# BeagleBone_Blue.net
KiCad netlist of a schematic drawn in EAGLE
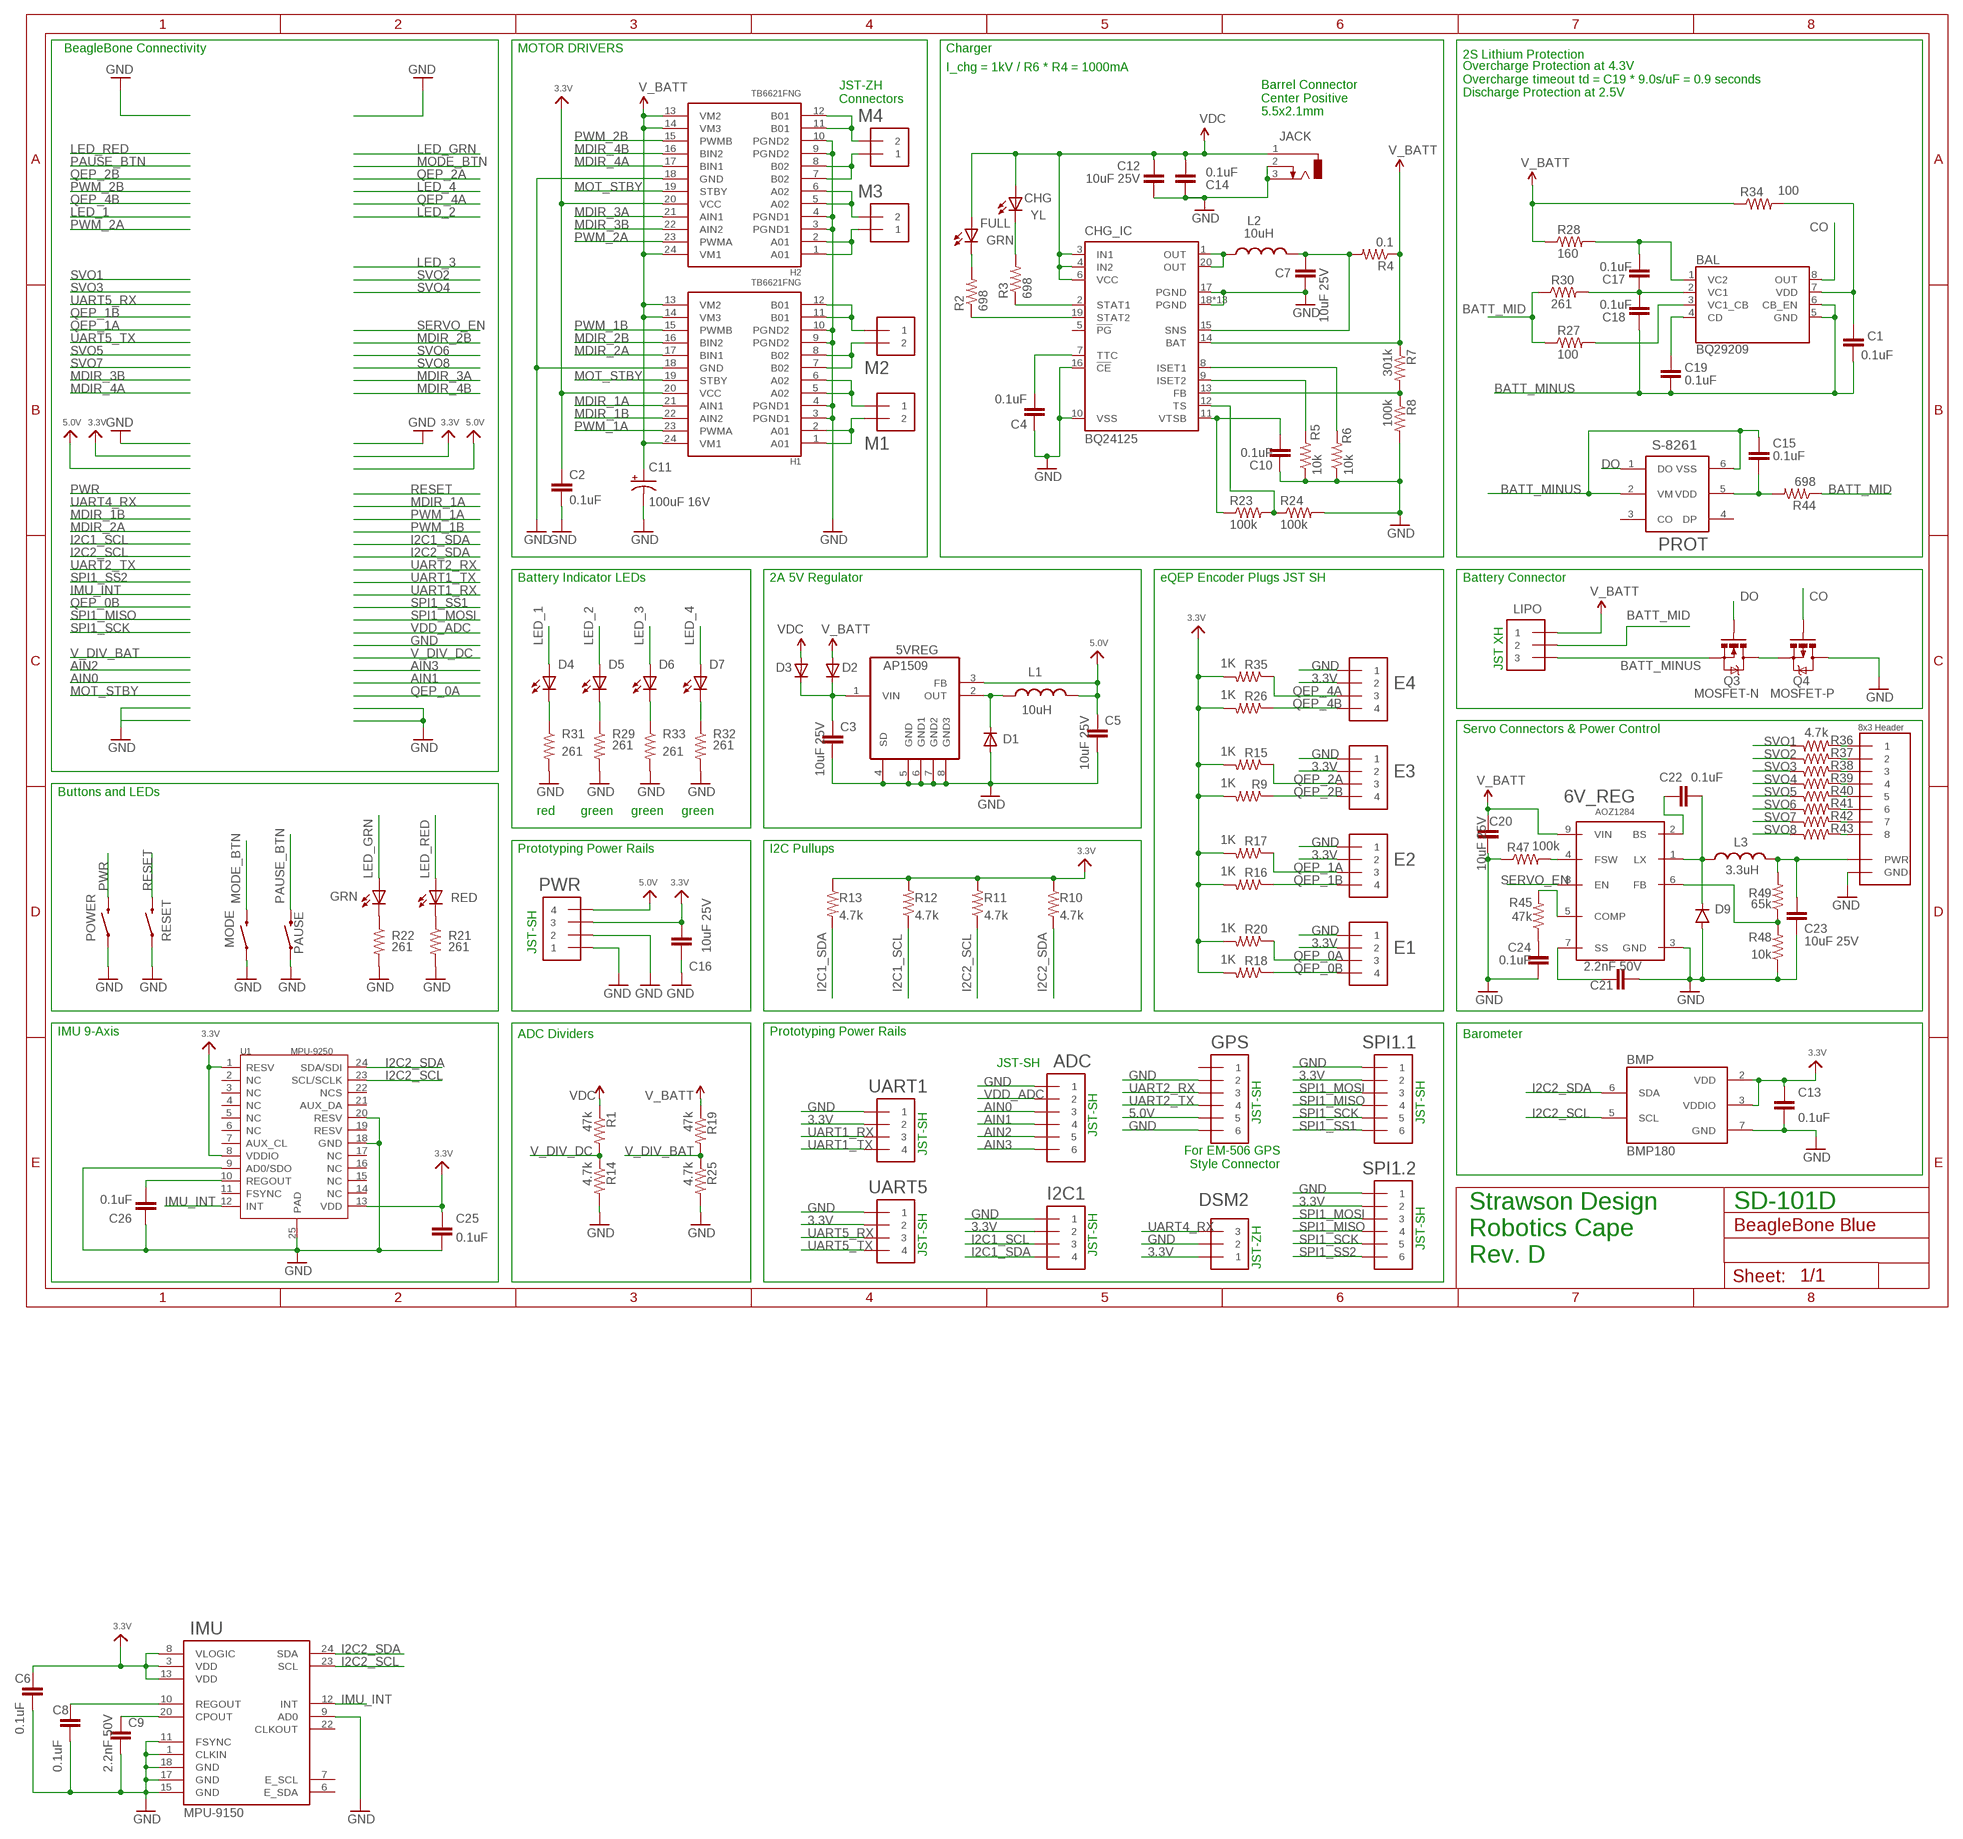
[diagram p0: schematic, sheet 1]

(export (version "E")
  (design (tool "Eeschema 10.0.6"))
  (components
    (comp (ref "5VREG")
      (value "AP1509SOIC-8-TIGHT")
      (footprint "eagle-import:SO08-TIGHT")
      (libsource (lib "eagle-import") (part "AP1509SOIC-8-TIGHT"))
    )
    (comp (ref "6V_REG")
      (value "AOZ1284")
      (footprint "eagle-import:SO08-EXPOSED")
      (libsource (lib "eagle-import") (part "AOZ1284"))
    )
    (comp (ref "ADC")
      (value "JST_SH_6")
      (footprint "eagle-import:JST_SH_6")
      (libsource (lib "eagle-import") (part "JST_SH_6"))
    )
    (comp (ref "BAL")
      (value "BQ29209")
      (footprint "eagle-import:8-SON_3X3MM")
      (libsource (lib "eagle-import") (part "BQ29209"))
    )
    (comp (ref "BMP")
      (value "BMP180")
      (footprint "eagle-import:BMP180")
      (libsource (lib "eagle-import") (part "BMP180"))
    )
    (comp (ref "C1")
      (value "0.1uF")
      (footprint "eagle-import:0402-CAP")
      (libsource (lib "eagle-import") (part "Strawson_Eagle_Lib_CAP0402-CAP"))
    )
    (comp (ref "C2")
      (value "0.1uF")
      (footprint "eagle-import:0402-CAP")
      (libsource (lib "eagle-import") (part "Strawson_Eagle_Lib_CAP0402-CAP"))
    )
    (comp (ref "C3")
      (value "10uF 25V")
      (footprint "eagle-import:0805")
      (libsource (lib "eagle-import") (part "CAP0805"))
    )
    (comp (ref "C4")
      (value "0.1uF")
      (footprint "eagle-import:0402-CAP")
      (libsource (lib "eagle-import") (part "Strawson_Eagle_Lib_CAP0402-CAP"))
    )
    (comp (ref "C5")
      (value "10uF 25V")
      (footprint "eagle-import:0805")
      (libsource (lib "eagle-import") (part "CAP0805"))
    )
    (comp (ref "C6")
      (value "0.1uF")
      (footprint "eagle-import:0402-CAP")
      (libsource (lib "eagle-import") (part "Strawson_Eagle_Lib_CAP0402-CAP"))
    )
    (comp (ref "C7")
      (value "10uF 25V")
      (footprint "eagle-import:0805")
      (libsource (lib "eagle-import") (part "CAP0805"))
    )
    (comp (ref "C8")
      (value "0.1uF")
      (footprint "eagle-import:0402-CAP")
      (libsource (lib "eagle-import") (part "Strawson_Eagle_Lib_CAP0402-CAP"))
    )
    (comp (ref "C9")
      (value "2.2nF 50V")
      (footprint "eagle-import:0402-CAP")
      (libsource (lib "eagle-import") (part "Strawson_Eagle_Lib_CAP0402-CAP"))
    )
    (comp (ref "C10")
      (value "0.1uF")
      (footprint "eagle-import:0402-CAP")
      (libsource (lib "eagle-import") (part "Strawson_Eagle_Lib_CAP0402-CAP"))
    )
    (comp (ref "C11")
      (value "100uF 16V")
      (footprint "eagle-import:PANASONIC_D")
      (libsource (lib "eagle-import") (part "CPOL-USD"))
    )
    (comp (ref "C12")
      (value "10uF 25V")
      (footprint "eagle-import:0805")
      (libsource (lib "eagle-import") (part "CAP0805"))
    )
    (comp (ref "C13")
      (value "0.1uF")
      (footprint "eagle-import:0402-CAP")
      (libsource (lib "eagle-import") (part "Strawson_Eagle_Lib_CAP0402-CAP"))
    )
    (comp (ref "C14")
      (value "0.1uF")
      (footprint "eagle-import:0402-CAP")
      (libsource (lib "eagle-import") (part "Strawson_Eagle_Lib_CAP0402-CAP"))
    )
    (comp (ref "C15")
      (value "0.1uF")
      (footprint "eagle-import:0402-CAP")
      (libsource (lib "eagle-import") (part "Strawson_Eagle_Lib_CAP0402-CAP"))
    )
    (comp (ref "C16")
      (value "10uF 25V")
      (footprint "eagle-import:0805")
      (libsource (lib "eagle-import") (part "CAP0805"))
    )
    (comp (ref "C17")
      (value "0.1uF")
      (footprint "eagle-import:0402-CAP")
      (libsource (lib "eagle-import") (part "Strawson_Eagle_Lib_CAP0402-CAP"))
    )
    (comp (ref "C18")
      (value "0.1uF")
      (footprint "eagle-import:0402-CAP")
      (libsource (lib "eagle-import") (part "Strawson_Eagle_Lib_CAP0402-CAP"))
    )
    (comp (ref "C19")
      (value "0.1uF")
      (footprint "eagle-import:0402-CAP")
      (libsource (lib "eagle-import") (part "Strawson_Eagle_Lib_CAP0402-CAP"))
    )
    (comp (ref "C20")
      (value "10uF 25V")
      (footprint "eagle-import:0805")
      (libsource (lib "eagle-import") (part "CAP0805"))
    )
    (comp (ref "C21")
      (value "2.2nF 50V")
      (footprint "eagle-import:0402-CAP")
      (libsource (lib "eagle-import") (part "Strawson_Eagle_Lib_CAP0402-CAP"))
    )
    (comp (ref "C22")
      (value "0.1uF")
      (footprint "eagle-import:0402-CAP")
      (libsource (lib "eagle-import") (part "Strawson_Eagle_Lib_CAP0402-CAP"))
    )
    (comp (ref "C23")
      (value "10uF 25V")
      (footprint "eagle-import:0805")
      (libsource (lib "eagle-import") (part "CAP0805"))
    )
    (comp (ref "C24")
      (value "0.1uF")
      (footprint "eagle-import:0402-CAP")
      (libsource (lib "eagle-import") (part "Strawson_Eagle_Lib_CAP0402-CAP"))
    )
    (comp (ref "C25")
      (value "0.1uF")
      (footprint "eagle-import:0402-CAP")
      (libsource (lib "eagle-import") (part "Strawson_Eagle_Lib_CAP0402-CAP"))
    )
    (comp (ref "C26")
      (value "0.1uF")
      (footprint "eagle-import:0402-CAP")
      (libsource (lib "eagle-import") (part "Strawson_Eagle_Lib_CAP0402-CAP"))
    )
    (comp (ref "CHG")
      (value "YL")
      (footprint "eagle-import:LED-0603")
      (libsource (lib "eagle-import") (part "LED0603"))
    )
    (comp (ref "CHG_IC")
      (value "BQ24125")
      (footprint "eagle-import:QFN20_3,5X4,5")
      (fields (field (name "MPN") "BQ24125RHLR"))
      (libsource (lib "eagle-import") (part "BQ24125"))
    )
    (comp (ref "D1")
      (value "DIODESOD-123")
      (footprint "eagle-import:SOD-123")
      (libsource (lib "eagle-import") (part "DIODESOD-123"))
    )
    (comp (ref "D2")
      (value "DIODESOD-123")
      (footprint "eagle-import:SOD-123")
      (libsource (lib "eagle-import") (part "DIODESOD-123"))
    )
    (comp (ref "D3")
      (value "DIODESOD-123")
      (footprint "eagle-import:SOD-123")
      (libsource (lib "eagle-import") (part "DIODESOD-123"))
    )
    (comp (ref "D4")
      (value "RED")
      (footprint "eagle-import:LED-0603")
      (libsource (lib "eagle-import") (part "LED0603"))
    )
    (comp (ref "D5")
      (value "GREEN")
      (footprint "eagle-import:LED-0603")
      (libsource (lib "eagle-import") (part "LED0603"))
    )
    (comp (ref "D6")
      (value "GREEN")
      (footprint "eagle-import:LED-0603")
      (libsource (lib "eagle-import") (part "LED0603"))
    )
    (comp (ref "D7")
      (value "GREEN")
      (footprint "eagle-import:LED-0603")
      (libsource (lib "eagle-import") (part "LED0603"))
    )
    (comp (ref "D9")
      (value "DIODEDO214AA")
      (footprint "eagle-import:DO-214AA")
      (libsource (lib "eagle-import") (part "DIODEDO214AA"))
    )
    (comp (ref "DSM2")
      (value "JST_ZH_3")
      (footprint "eagle-import:JST_ZH_3")
      (libsource (lib "eagle-import") (part "JST_ZH_3"))
    )
    (comp (ref "E1")
      (value "JST_SH_4")
      (footprint "eagle-import:JST_SH_4_SMD")
      (libsource (lib "eagle-import") (part "JST_SH_4"))
    )
    (comp (ref "E2")
      (value "JST_SH_4")
      (footprint "eagle-import:JST_SH_4_SMD")
      (libsource (lib "eagle-import") (part "JST_SH_4"))
    )
    (comp (ref "E3")
      (value "JST_SH_4")
      (footprint "eagle-import:JST_SH_4_SMD")
      (libsource (lib "eagle-import") (part "JST_SH_4"))
    )
    (comp (ref "E4")
      (value "JST_SH_4")
      (footprint "eagle-import:JST_SH_4_SMD")
      (libsource (lib "eagle-import") (part "JST_SH_4"))
    )
    (comp (ref "FULL")
      (value "GRN")
      (footprint "eagle-import:LED-0603")
      (libsource (lib "eagle-import") (part "LED0603"))
    )
    (comp (ref "GPS")
      (value "JST_SH_6")
      (footprint "eagle-import:JST_SH_6")
      (libsource (lib "eagle-import") (part "JST_SH_6"))
    )
    (comp (ref "GRN")
      (value "GRN")
      (footprint "eagle-import:LED-0603")
      (libsource (lib "eagle-import") (part "LED0603"))
    )
    (comp (ref "H1")
      (value "TB6621FNG")
      (footprint "eagle-import:SSOP24")
      (libsource (lib "eagle-import") (part "TB6621FNG"))
    )
    (comp (ref "H2")
      (value "TB6621FNG")
      (footprint "eagle-import:SSOP24")
      (libsource (lib "eagle-import") (part "TB6621FNG"))
    )
    (comp (ref "I2C1")
      (value "JST_SH_4")
      (footprint "eagle-import:JST_SH_4_SMD")
      (libsource (lib "eagle-import") (part "JST_SH_4"))
    )
    (comp (ref "IMU")
      (value "MPU-9150")
      (footprint "eagle-import:QFN-24-NP")
      (libsource (lib "eagle-import") (part "MPU-9150QFN-24-NP"))
    )
    (comp (ref "JACK")
      (value "5.5x2.1mm")
      (footprint "eagle-import:DCJ0303")
      (libsource (lib "eagle-import") (part "DCJ0303"))
    )
    (comp (ref "L1")
      (value "10uH")
      (footprint "eagle-import:SRN6045")
      (libsource (lib "eagle-import") (part "INDUCTORBOURNS_SRN6045"))
    )
    (comp (ref "L2")
      (value "10uH")
      (footprint "eagle-import:SRN6045")
      (libsource (lib "eagle-import") (part "INDUCTORBOURNS_SRN6045"))
    )
    (comp (ref "L3")
      (value "3.3uH")
      (footprint "eagle-import:8X8MM_INDUCTOR")
      (libsource (lib "eagle-import") (part "INDUCTOR"))
    )
    (comp (ref "LIPO")
      (value "JST_XH_3-PIN")
      (footprint "eagle-import:JST_XH_3-PIN")
      (libsource (lib "eagle-import") (part "JST_XH_3-PIN"))
    )
    (comp (ref "M1")
      (value "JST_ZH_2")
      (footprint "eagle-import:JST_ZH_2")
      (libsource (lib "eagle-import") (part "JST_ZH_2"))
    )
    (comp (ref "M2")
      (value "JST_ZH_2")
      (footprint "eagle-import:JST_ZH_2")
      (libsource (lib "eagle-import") (part "JST_ZH_2"))
    )
    (comp (ref "M3")
      (value "JST_ZH_2")
      (footprint "eagle-import:JST_ZH_2")
      (libsource (lib "eagle-import") (part "JST_ZH_2"))
    )
    (comp (ref "M4")
      (value "JST_ZH_2")
      (footprint "eagle-import:JST_ZH_2")
      (libsource (lib "eagle-import") (part "JST_ZH_2"))
    )
    (comp (ref "MODE")
      (value "SWITCH-MOMENTARY-2-SMD-1101NE")
      (footprint "eagle-import:TACTILE-SWITCH-1101NE")
      (libsource (lib "eagle-import") (part "SWITCH-MOMENTARY-2-SMD-1101NE"))
    )
    (comp (ref "PAUSE")
      (value "SWITCH-MOMENTARY-2-SMD-1101NE")
      (footprint "eagle-import:TACTILE-SWITCH-1101NE")
      (libsource (lib "eagle-import") (part "SWITCH-MOMENTARY-2-SMD-1101NE"))
    )
    (comp (ref "POWER")
      (value "SWITCH-MOMENTARY-2-SMD-1101NE")
      (footprint "eagle-import:TACTILE-SWITCH-1101NE")
      (libsource (lib "eagle-import") (part "SWITCH-MOMENTARY-2-SMD-1101NE"))
    )
    (comp (ref "PROT")
      (value "S-8261")
      (footprint "eagle-import:SOT-236")
      (libsource (lib "eagle-import") (part "S-8261"))
    )
    (comp (ref "PWR")
      (value "JST_SH_4")
      (footprint "eagle-import:JST_SH_4_SMD")
      (libsource (lib "eagle-import") (part "JST_SH_4"))
    )
    (comp (ref "Q3")
      (value "MOSFET-N")
      (footprint "eagle-import:SO08-TIGHT")
      (libsource (lib "eagle-import") (part "MOSFET-NCHANNEL"))
    )
    (comp (ref "Q4")
      (value "MOSFET-P")
      (footprint "eagle-import:SO08-TIGHT")
      (libsource (lib "eagle-import") (part "MOSFET-PCHANNEL"))
    )
    (comp (ref "R1")
      (value "47k")
      (footprint "eagle-import:0402-RES")
      (libsource (lib "eagle-import") (part "RESISTOR0402-RES"))
    )
    (comp (ref "R2")
      (value "698")
      (footprint "eagle-import:0402-RES")
      (libsource (lib "eagle-import") (part "RESISTOR0402-RES"))
    )
    (comp (ref "R3")
      (value "698")
      (footprint "eagle-import:0402-RES")
      (libsource (lib "eagle-import") (part "RESISTOR0402-RES"))
    )
    (comp (ref "R4")
      (value "0.1")
      (footprint "eagle-import:0603-RES")
      (libsource (lib "eagle-import") (part "RESISTOR0603"))
    )
    (comp (ref "R5")
      (value "10k")
      (footprint "eagle-import:0402-RES")
      (libsource (lib "eagle-import") (part "RESISTOR0402-RES"))
    )
    (comp (ref "R6")
      (value "10k")
      (footprint "eagle-import:0402-RES")
      (libsource (lib "eagle-import") (part "RESISTOR0402-RES"))
    )
    (comp (ref "R7")
      (value "301k")
      (footprint "eagle-import:0402-RES")
      (libsource (lib "eagle-import") (part "RESISTOR0402-RES"))
    )
    (comp (ref "R8")
      (value "100k")
      (footprint "eagle-import:0402-RES")
      (libsource (lib "eagle-import") (part "RESISTOR0402-RES"))
    )
    (comp (ref "R9")
      (value "1K")
      (footprint "eagle-import:0402-RES")
      (libsource (lib "eagle-import") (part "RESISTOR0402-RES"))
    )
    (comp (ref "R10")
      (value "4.7k")
      (footprint "eagle-import:0402-RES")
      (libsource (lib "eagle-import") (part "RESISTOR0402-RES"))
    )
    (comp (ref "R11")
      (value "4.7k")
      (footprint "eagle-import:0402-RES")
      (libsource (lib "eagle-import") (part "RESISTOR0402-RES"))
    )
    (comp (ref "R12")
      (value "4.7k")
      (footprint "eagle-import:0402-RES")
      (libsource (lib "eagle-import") (part "RESISTOR0402-RES"))
    )
    (comp (ref "R13")
      (value "4.7k")
      (footprint "eagle-import:0402-RES")
      (libsource (lib "eagle-import") (part "RESISTOR0402-RES"))
    )
    (comp (ref "R14")
      (value "4.7k")
      (footprint "eagle-import:0402-RES")
      (libsource (lib "eagle-import") (part "RESISTOR0402-RES"))
    )
    (comp (ref "R15")
      (value "1K")
      (footprint "eagle-import:0402-RES")
      (libsource (lib "eagle-import") (part "RESISTOR0402-RES"))
    )
    (comp (ref "R16")
      (value "1K")
      (footprint "eagle-import:0402-RES")
      (libsource (lib "eagle-import") (part "RESISTOR0402-RES"))
    )
    (comp (ref "R17")
      (value "1K")
      (footprint "eagle-import:0402-RES")
      (libsource (lib "eagle-import") (part "RESISTOR0402-RES"))
    )
    (comp (ref "R18")
      (value "1K")
      (footprint "eagle-import:0402-RES")
      (libsource (lib "eagle-import") (part "RESISTOR0402-RES"))
    )
    (comp (ref "R19")
      (value "47k")
      (footprint "eagle-import:0402-RES")
      (libsource (lib "eagle-import") (part "RESISTOR0402-RES"))
    )
    (comp (ref "R20")
      (value "1K")
      (footprint "eagle-import:0402-RES")
      (libsource (lib "eagle-import") (part "RESISTOR0402-RES"))
    )
    (comp (ref "R21")
      (value "261")
      (footprint "eagle-import:0402-RES")
      (libsource (lib "eagle-import") (part "RESISTOR0402-RES"))
    )
    (comp (ref "R22")
      (value "261")
      (footprint "eagle-import:0402-RES")
      (libsource (lib "eagle-import") (part "RESISTOR0402-RES"))
    )
    (comp (ref "R23")
      (value "100k")
      (footprint "eagle-import:0402-RES")
      (libsource (lib "eagle-import") (part "RESISTOR0402-RES"))
    )
    (comp (ref "R24")
      (value "100k")
      (footprint "eagle-import:0402-RES")
      (libsource (lib "eagle-import") (part "RESISTOR0402-RES"))
    )
    (comp (ref "R25")
      (value "4.7k")
      (footprint "eagle-import:0402-RES")
      (libsource (lib "eagle-import") (part "RESISTOR0402-RES"))
    )
    (comp (ref "R26")
      (value "1K")
      (footprint "eagle-import:0402-RES")
      (libsource (lib "eagle-import") (part "RESISTOR0402-RES"))
    )
    (comp (ref "R27")
      (value "100")
      (footprint "eagle-import:0402-RES")
      (libsource (lib "eagle-import") (part "RESISTOR0402-RES"))
    )
    (comp (ref "R28")
      (value "160")
      (footprint "eagle-import:0402-RES")
      (libsource (lib "eagle-import") (part "RESISTOR0402-RES"))
    )
    (comp (ref "R29")
      (value "261")
      (footprint "eagle-import:0402-RES")
      (libsource (lib "eagle-import") (part "RESISTOR0402-RES"))
    )
    (comp (ref "R30")
      (value "261")
      (footprint "eagle-import:0402-RES")
      (libsource (lib "eagle-import") (part "RESISTOR0402-RES"))
    )
    (comp (ref "R31")
      (value "261")
      (footprint "eagle-import:0402-RES")
      (libsource (lib "eagle-import") (part "RESISTOR0402-RES"))
    )
    (comp (ref "R32")
      (value "261")
      (footprint "eagle-import:0402-RES")
      (libsource (lib "eagle-import") (part "RESISTOR0402-RES"))
    )
    (comp (ref "R33")
      (value "261")
      (footprint "eagle-import:0402-RES")
      (libsource (lib "eagle-import") (part "RESISTOR0402-RES"))
    )
    (comp (ref "R34")
      (value "100")
      (footprint "eagle-import:0402-RES")
      (libsource (lib "eagle-import") (part "RESISTOR0402-RES"))
    )
    (comp (ref "R35")
      (value "1K")
      (footprint "eagle-import:0402-RES")
      (libsource (lib "eagle-import") (part "RESISTOR0402-RES"))
    )
    (comp (ref "R36")
      (value "4.7k")
      (footprint "eagle-import:0402-RES")
      (libsource (lib "eagle-import") (part "RESISTOR0402-RES"))
    )
    (comp (ref "R37")
      (value "4.7k")
      (footprint "eagle-import:0402-RES")
      (libsource (lib "eagle-import") (part "RESISTOR0402-RES"))
    )
    (comp (ref "R38")
      (value "4.7k")
      (footprint "eagle-import:0402-RES")
      (libsource (lib "eagle-import") (part "RESISTOR0402-RES"))
    )
    (comp (ref "R39")
      (value "4.7k")
      (footprint "eagle-import:0402-RES")
      (libsource (lib "eagle-import") (part "RESISTOR0402-RES"))
    )
    (comp (ref "R40")
      (value "4.7k")
      (footprint "eagle-import:0402-RES")
      (libsource (lib "eagle-import") (part "RESISTOR0402-RES"))
    )
    (comp (ref "R41")
      (value "4.7k")
      (footprint "eagle-import:0402-RES")
      (libsource (lib "eagle-import") (part "RESISTOR0402-RES"))
    )
    (comp (ref "R42")
      (value "4.7k")
      (footprint "eagle-import:0402-RES")
      (libsource (lib "eagle-import") (part "RESISTOR0402-RES"))
    )
    (comp (ref "R43")
      (value "4.7k")
      (footprint "eagle-import:0402-RES")
      (libsource (lib "eagle-import") (part "RESISTOR0402-RES"))
    )
    (comp (ref "R44")
      (value "698")
      (footprint "eagle-import:0402-RES")
      (libsource (lib "eagle-import") (part "RESISTOR0402-RES"))
    )
    (comp (ref "R45")
      (value "47k")
      (footprint "eagle-import:0402-RES")
      (libsource (lib "eagle-import") (part "RESISTOR0402-RES"))
    )
    (comp (ref "R47")
      (value "100k")
      (footprint "eagle-import:0402-RES")
      (libsource (lib "eagle-import") (part "RESISTOR0402-RES"))
    )
    (comp (ref "R48")
      (value "10k")
      (footprint "eagle-import:0402-RES")
      (libsource (lib "eagle-import") (part "RESISTOR0402-RES"))
    )
    (comp (ref "R49")
      (value "65k")
      (footprint "eagle-import:0402-RES")
      (libsource (lib "eagle-import") (part "RESISTOR0402-RES"))
    )
    (comp (ref "RED")
      (value "RED")
      (footprint "eagle-import:LED-0603")
      (libsource (lib "eagle-import") (part "LED0603"))
    )
    (comp (ref "RESET")
      (value "SWITCH-MOMENTARY-2-SMD-1101NE")
      (footprint "eagle-import:TACTILE-SWITCH-1101NE")
      (libsource (lib "eagle-import") (part "SWITCH-MOMENTARY-2-SMD-1101NE"))
    )
    (comp (ref "SPI1.1")
      (value "JST_SH_6")
      (footprint "eagle-import:JST_SH_6")
      (libsource (lib "eagle-import") (part "JST_SH_6"))
    )
    (comp (ref "SPI1.2")
      (value "JST_SH_6")
      (footprint "eagle-import:JST_SH_6")
      (libsource (lib "eagle-import") (part "JST_SH_6"))
    )
    (comp (ref "U$1")
      (value "SERVO_HEADERS_8X")
      (footprint "eagle-import:3X8_0.1__HEADER")
      (libsource (lib "eagle-import") (part "SERVO_HEADERS_8X"))
    )
    (comp (ref "U1")
      (value "MPU-9250")
      (footprint "eagle-import:QFN24G-0.4-3X3MM")
      (libsource (lib "eagle-import") (part "MPU-9250"))
    )
    (comp (ref "UART1")
      (value "JST_SH_4")
      (footprint "eagle-import:JST_SH_4_SMD")
      (libsource (lib "eagle-import") (part "JST_SH_4"))
    )
    (comp (ref "UART5")
      (value "JST_SH_4")
      (footprint "eagle-import:JST_SH_4_SMD")
      (libsource (lib "eagle-import") (part "JST_SH_4"))
    )
  )
  (nets
    (net (code "1") (name "/AIN0") (class "Default")
      (node (ref "ADC") (pin "3") (pinfunction "3_3") (pintype "bidirectional"))
    )
    (net (code "2") (name "/AIN1") (class "Default")
      (node (ref "ADC") (pin "4") (pinfunction "4_4") (pintype "bidirectional"))
    )
    (net (code "3") (name "/AIN2") (class "Default")
      (node (ref "ADC") (pin "5") (pinfunction "5_5") (pintype "bidirectional"))
    )
    (net (code "4") (name "/AIN3") (class "Default")
      (node (ref "ADC") (pin "6") (pinfunction "6_6") (pintype "bidirectional"))
    )
    (net (code "5") (name "/BATT_MID") (class "Default")
      (node (ref "LIPO") (pin "P$2") (pinfunction "2_P$2") (pintype "passive"))
      (node (ref "R27") (pin "1") (pinfunction "1_1") (pintype "passive"))
      (node (ref "R30") (pin "1") (pinfunction "1_1") (pintype "passive"))
      (node (ref "R44") (pin "1") (pinfunction "1_1") (pintype "passive"))
    )
    (net (code "6") (name "/BATT_MINUS") (class "Default")
      (node (ref "BAL") (pin "5") (pinfunction "GND_5") (pintype "bidirectional"))
      (node (ref "BAL") (pin "6") (pinfunction "CB_EN_6") (pintype "bidirectional"))
      (node (ref "C1") (pin "2") (pinfunction "2_2") (pintype "passive"))
      (node (ref "C15") (pin "1") (pinfunction "1_1") (pintype "passive"))
      (node (ref "C18") (pin "1") (pinfunction "1_1") (pintype "passive"))
      (node (ref "C19") (pin "2") (pinfunction "2_2") (pintype "passive"))
      (node (ref "LIPO") (pin "P$3") (pinfunction "3_P$3") (pintype "passive"))
      (node (ref "PROT") (pin "2") (pinfunction "VM_2") (pintype "bidirectional"))
      (node (ref "PROT") (pin "6") (pinfunction "VSS_6") (pintype "bidirectional"))
      (node (ref "Q3") (pin "1") (pinfunction "S_1") (pintype "passive"))
      (node (ref "Q3") (pin "2") (pinfunction "S_2") (pintype "passive"))
      (node (ref "Q3") (pin "3") (pinfunction "S_3") (pintype "passive"))
    )
    (net (code "7") (name "/CO") (class "Default")
      (node (ref "BAL") (pin "8") (pinfunction "OUT_8") (pintype "bidirectional"))
      (node (ref "Q4") (pin "4") (pinfunction "G_4") (pintype "passive"))
    )
    (net (code "8") (name "/DO") (class "Default")
      (node (ref "PROT") (pin "1") (pinfunction "DO_1") (pintype "bidirectional"))
      (node (ref "Q3") (pin "4") (pinfunction "G_4") (pintype "passive"))
    )
    (net (code "9") (name "/I2C1_SCL") (class "Default")
      (node (ref "I2C1") (pin "3") (pinfunction "3_3") (pintype "bidirectional"))
      (node (ref "R12") (pin "1") (pinfunction "1_1") (pintype "passive"))
    )
    (net (code "10") (name "/I2C1_SDA") (class "Default")
      (node (ref "I2C1") (pin "4") (pinfunction "4_4") (pintype "bidirectional"))
      (node (ref "R13") (pin "2") (pinfunction "2_2") (pintype "passive"))
    )
    (net (code "11") (name "/I2C2_SCL") (class "Default")
      (node (ref "BMP") (pin "5") (pinfunction "SCL_5") (pintype "input"))
      (node (ref "IMU") (pin "23") (pinfunction "SCL_23") (pintype "bidirectional"))
      (node (ref "R11") (pin "1") (pinfunction "1_1") (pintype "passive"))
      (node (ref "U1") (pin "23") (pinfunction "SCL/SCLK_23") (pintype "bidirectional"))
    )
    (net (code "12") (name "/I2C2_SDA") (class "Default")
      (node (ref "BMP") (pin "6") (pinfunction "SDA_6") (pintype "bidirectional"))
      (node (ref "IMU") (pin "24") (pinfunction "SDA_24") (pintype "bidirectional"))
      (node (ref "R10") (pin "2") (pinfunction "2_2") (pintype "passive"))
      (node (ref "U1") (pin "24") (pinfunction "SDA/SDI_24") (pintype "bidirectional"))
    )
    (net (code "13") (name "/IMU_INT") (class "Default")
      (node (ref "IMU") (pin "12") (pinfunction "INT_12") (pintype "bidirectional"))
      (node (ref "U1") (pin "12") (pinfunction "INT_12") (pintype "bidirectional"))
    )
    (net (code "14") (name "/LED_1") (class "Default")
      (node (ref "D4") (pin "A") (pinfunction "A_A") (pintype "passive"))
    )
    (net (code "15") (name "/LED_2") (class "Default")
      (node (ref "D5") (pin "A") (pinfunction "A_A") (pintype "passive"))
    )
    (net (code "16") (name "/LED_3") (class "Default")
      (node (ref "D6") (pin "A") (pinfunction "A_A") (pintype "passive"))
    )
    (net (code "17") (name "/LED_4") (class "Default")
      (node (ref "D7") (pin "A") (pinfunction "A_A") (pintype "passive"))
    )
    (net (code "18") (name "/LED_GRN") (class "Default")
      (node (ref "GRN") (pin "A") (pinfunction "A_A") (pintype "passive"))
    )
    (net (code "19") (name "/LED_RED") (class "Default")
      (node (ref "RED") (pin "A") (pinfunction "A_A") (pintype "passive"))
    )
    (net (code "20") (name "/MDIR_1A") (class "Default")
      (node (ref "H1") (pin "21") (pinfunction "AIN1_21") (pintype "bidirectional"))
    )
    (net (code "21") (name "/MDIR_1B") (class "Default")
      (node (ref "H1") (pin "22") (pinfunction "AIN2_22") (pintype "bidirectional"))
    )
    (net (code "22") (name "/MDIR_2A") (class "Default")
      (node (ref "H1") (pin "17") (pinfunction "BIN1_17") (pintype "bidirectional"))
    )
    (net (code "23") (name "/MDIR_2B") (class "Default")
      (node (ref "H1") (pin "16") (pinfunction "BIN2_16") (pintype "bidirectional"))
    )
    (net (code "24") (name "/MDIR_3A") (class "Default")
      (node (ref "H2") (pin "21") (pinfunction "AIN1_21") (pintype "bidirectional"))
    )
    (net (code "25") (name "/MDIR_3B") (class "Default")
      (node (ref "H2") (pin "22") (pinfunction "AIN2_22") (pintype "bidirectional"))
    )
    (net (code "26") (name "/MDIR_4A") (class "Default")
      (node (ref "H2") (pin "17") (pinfunction "BIN1_17") (pintype "bidirectional"))
    )
    (net (code "27") (name "/MDIR_4B") (class "Default")
      (node (ref "H2") (pin "16") (pinfunction "BIN2_16") (pintype "bidirectional"))
    )
    (net (code "28") (name "/MODE_BTN") (class "Default")
      (node (ref "MODE") (pin "P$2") (pinfunction "2_P$2") (pintype "passive"))
    )
    (net (code "29") (name "/MOT_STBY") (class "Default")
      (node (ref "H1") (pin "19") (pinfunction "STBY_19") (pintype "bidirectional"))
      (node (ref "H2") (pin "19") (pinfunction "STBY_19") (pintype "bidirectional"))
    )
    (net (code "30") (name "/PAUSE_BTN") (class "Default")
      (node (ref "PAUSE") (pin "P$2") (pinfunction "2_P$2") (pintype "passive"))
    )
    (net (code "31") (name "/PWM_1A") (class "Default")
      (node (ref "H1") (pin "23") (pinfunction "PWMA_23") (pintype "bidirectional"))
    )
    (net (code "32") (name "/PWM_1B") (class "Default")
      (node (ref "H1") (pin "15") (pinfunction "PWMB_15") (pintype "bidirectional"))
    )
    (net (code "33") (name "/PWM_2A") (class "Default")
      (node (ref "H2") (pin "23") (pinfunction "PWMA_23") (pintype "bidirectional"))
    )
    (net (code "34") (name "/PWM_2B") (class "Default")
      (node (ref "H2") (pin "15") (pinfunction "PWMB_15") (pintype "bidirectional"))
    )
    (net (code "35") (name "/PWR") (class "Default")
      (node (ref "POWER") (pin "P$2") (pinfunction "2_P$2") (pintype "passive"))
    )
    (net (code "36") (name "/QEP_0A") (class "Default")
      (node (ref "E1") (pin "3") (pinfunction "3_3") (pintype "bidirectional"))
      (node (ref "R20") (pin "1") (pinfunction "1_1") (pintype "passive"))
    )
    (net (code "37") (name "/QEP_0B") (class "Default")
      (node (ref "E1") (pin "4") (pinfunction "4_4") (pintype "bidirectional"))
      (node (ref "R18") (pin "1") (pinfunction "1_1") (pintype "passive"))
    )
    (net (code "38") (name "/QEP_1A") (class "Default")
      (node (ref "E2") (pin "3") (pinfunction "3_3") (pintype "bidirectional"))
      (node (ref "R17") (pin "1") (pinfunction "1_1") (pintype "passive"))
    )
    (net (code "39") (name "/QEP_1B") (class "Default")
      (node (ref "E2") (pin "4") (pinfunction "4_4") (pintype "bidirectional"))
      (node (ref "R16") (pin "1") (pinfunction "1_1") (pintype "passive"))
    )
    (net (code "40") (name "/QEP_2A") (class "Default")
      (node (ref "E3") (pin "3") (pinfunction "3_3") (pintype "bidirectional"))
      (node (ref "R15") (pin "1") (pinfunction "1_1") (pintype "passive"))
    )
    (net (code "41") (name "/QEP_2B") (class "Default")
      (node (ref "E3") (pin "4") (pinfunction "4_4") (pintype "bidirectional"))
      (node (ref "R9") (pin "1") (pinfunction "1_1") (pintype "passive"))
    )
    (net (code "42") (name "/QEP_4A") (class "Default")
      (node (ref "E4") (pin "3") (pinfunction "3_3") (pintype "bidirectional"))
      (node (ref "R35") (pin "1") (pinfunction "1_1") (pintype "passive"))
    )
    (net (code "43") (name "/QEP_4B") (class "Default")
      (node (ref "E4") (pin "4") (pinfunction "4_4") (pintype "bidirectional"))
      (node (ref "R26") (pin "1") (pinfunction "1_1") (pintype "passive"))
    )
    (net (code "44") (name "/RESET") (class "Default")
      (node (ref "RESET") (pin "P$2") (pinfunction "2_P$2") (pintype "passive"))
    )
    (net (code "45") (name "/SERVO_EN") (class "Default")
      (node (ref "6V_REG") (pin "8") (pinfunction "EN_8") (pintype "bidirectional"))
    )
    (net (code "46") (name "/SPI1_MISO") (class "Default")
      (node (ref "SPI1.1") (pin "4") (pinfunction "4_4") (pintype "bidirectional"))
      (node (ref "SPI1.2") (pin "4") (pinfunction "4_4") (pintype "bidirectional"))
    )
    (net (code "47") (name "/SPI1_MOSI") (class "Default")
      (node (ref "SPI1.1") (pin "3") (pinfunction "3_3") (pintype "bidirectional"))
      (node (ref "SPI1.2") (pin "3") (pinfunction "3_3") (pintype "bidirectional"))
    )
    (net (code "48") (name "/SPI1_SCK") (class "Default")
      (node (ref "SPI1.1") (pin "5") (pinfunction "5_5") (pintype "bidirectional"))
      (node (ref "SPI1.2") (pin "5") (pinfunction "5_5") (pintype "bidirectional"))
    )
    (net (code "49") (name "/SPI1_SS1") (class "Default")
      (node (ref "SPI1.1") (pin "6") (pinfunction "6_6") (pintype "bidirectional"))
    )
    (net (code "50") (name "/SPI1_SS2") (class "Default")
      (node (ref "SPI1.2") (pin "6") (pinfunction "6_6") (pintype "bidirectional"))
    )
    (net (code "51") (name "/SVO1") (class "Default")
      (node (ref "R36") (pin "1") (pinfunction "1_1") (pintype "passive"))
    )
    (net (code "52") (name "/SVO2") (class "Default")
      (node (ref "R37") (pin "1") (pinfunction "1_1") (pintype "passive"))
    )
    (net (code "53") (name "/SVO3") (class "Default")
      (node (ref "R38") (pin "1") (pinfunction "1_1") (pintype "passive"))
    )
    (net (code "54") (name "/SVO4") (class "Default")
      (node (ref "R39") (pin "1") (pinfunction "1_1") (pintype "passive"))
    )
    (net (code "55") (name "/SVO5") (class "Default")
      (node (ref "R40") (pin "1") (pinfunction "1_1") (pintype "passive"))
    )
    (net (code "56") (name "/SVO6") (class "Default")
      (node (ref "R41") (pin "1") (pinfunction "1_1") (pintype "passive"))
    )
    (net (code "57") (name "/SVO7") (class "Default")
      (node (ref "R42") (pin "1") (pinfunction "1_1") (pintype "passive"))
    )
    (net (code "58") (name "/SVO8") (class "Default")
      (node (ref "R43") (pin "1") (pinfunction "1_1") (pintype "passive"))
    )
    (net (code "59") (name "/UART1_RX") (class "Default")
      (node (ref "UART1") (pin "3") (pinfunction "3_3") (pintype "bidirectional"))
    )
    (net (code "60") (name "/UART1_TX") (class "Default")
      (node (ref "UART1") (pin "4") (pinfunction "4_4") (pintype "bidirectional"))
    )
    (net (code "61") (name "/UART2_RX") (class "Default")
      (node (ref "GPS") (pin "3") (pinfunction "3_3") (pintype "bidirectional"))
    )
    (net (code "62") (name "/UART2_TX") (class "Default")
      (node (ref "GPS") (pin "4") (pinfunction "4_4") (pintype "bidirectional"))
    )
    (net (code "63") (name "/UART4_RX") (class "Default")
      (node (ref "DSM2") (pin "P$3") (pinfunction "3_P$3") (pintype "bidirectional"))
    )
    (net (code "64") (name "/UART5_RX") (class "Default")
      (node (ref "UART5") (pin "3") (pinfunction "3_3") (pintype "bidirectional"))
    )
    (net (code "65") (name "/UART5_TX") (class "Default")
      (node (ref "UART5") (pin "4") (pinfunction "4_4") (pintype "bidirectional"))
    )
    (net (code "66") (name "/VDD_ADC") (class "Default")
      (node (ref "ADC") (pin "2") (pinfunction "2_2") (pintype "bidirectional"))
    )
    (net (code "67") (name "/V_DIV_BAT") (class "Default")
      (node (ref "R19") (pin "2") (pinfunction "2_2") (pintype "passive"))
      (node (ref "R25") (pin "1") (pinfunction "1_1") (pintype "passive"))
    )
    (net (code "68") (name "/V_DIV_DC") (class "Default")
      (node (ref "R1") (pin "2") (pinfunction "2_2") (pintype "passive"))
      (node (ref "R14") (pin "1") (pinfunction "1_1") (pintype "passive"))
    )
    (net (code "69") (name "3.3V") (class "Default")
      (node (ref "BMP") (pin "2") (pinfunction "VDD_2") (pintype "power_in"))
      (node (ref "BMP") (pin "3") (pinfunction "VDDIO_3") (pintype "power_in"))
      (node (ref "C13") (pin "1") (pinfunction "1_1") (pintype "passive"))
      (node (ref "C16") (pin "1") (pinfunction "1_1") (pintype "passive"))
      (node (ref "C2") (pin "2") (pinfunction "2_2") (pintype "passive"))
      (node (ref "C25") (pin "1") (pinfunction "1_1") (pintype "passive"))
      (node (ref "C6") (pin "1") (pinfunction "1_1") (pintype "passive"))
      (node (ref "DSM2") (pin "P$1") (pinfunction "1_P$1") (pintype "bidirectional"))
      (node (ref "E1") (pin "2") (pinfunction "2_2") (pintype "bidirectional"))
      (node (ref "E2") (pin "2") (pinfunction "2_2") (pintype "bidirectional"))
      (node (ref "E3") (pin "2") (pinfunction "2_2") (pintype "bidirectional"))
      (node (ref "E4") (pin "2") (pinfunction "2_2") (pintype "bidirectional"))
      (node (ref "H1") (pin "20") (pinfunction "VCC_20") (pintype "bidirectional"))
      (node (ref "H2") (pin "20") (pinfunction "VCC_20") (pintype "bidirectional"))
      (node (ref "I2C1") (pin "2") (pinfunction "2_2") (pintype "bidirectional"))
      (node (ref "IMU") (pin "13") (pinfunction "VDD_13") (pintype "bidirectional"))
      (node (ref "IMU") (pin "3") (pinfunction "VDD_3") (pintype "bidirectional"))
      (node (ref "IMU") (pin "8") (pinfunction "VLOGIC_8") (pintype "bidirectional"))
      (node (ref "PWR") (pin "3") (pinfunction "3_3") (pintype "bidirectional"))
      (node (ref "R10") (pin "1") (pinfunction "1_1") (pintype "passive"))
      (node (ref "R11") (pin "2") (pinfunction "2_2") (pintype "passive"))
      (node (ref "R12") (pin "2") (pinfunction "2_2") (pintype "passive"))
      (node (ref "R13") (pin "1") (pinfunction "1_1") (pintype "passive"))
      (node (ref "R15") (pin "2") (pinfunction "2_2") (pintype "passive"))
      (node (ref "R16") (pin "2") (pinfunction "2_2") (pintype "passive"))
      (node (ref "R17") (pin "2") (pinfunction "2_2") (pintype "passive"))
      (node (ref "R18") (pin "2") (pinfunction "2_2") (pintype "passive"))
      (node (ref "R20") (pin "2") (pinfunction "2_2") (pintype "passive"))
      (node (ref "R26") (pin "2") (pinfunction "2_2") (pintype "passive"))
      (node (ref "R35") (pin "2") (pinfunction "2_2") (pintype "passive"))
      (node (ref "R9") (pin "2") (pinfunction "2_2") (pintype "passive"))
      (node (ref "SPI1.1") (pin "2") (pinfunction "2_2") (pintype "bidirectional"))
      (node (ref "SPI1.2") (pin "2") (pinfunction "2_2") (pintype "bidirectional"))
      (node (ref "U1") (pin "1") (pinfunction "RESV_1") (pintype "bidirectional"))
      (node (ref "U1") (pin "13") (pinfunction "VDD_13") (pintype "bidirectional"))
      (node (ref "U1") (pin "8") (pinfunction "VDDIO_8") (pintype "bidirectional"))
      (node (ref "UART1") (pin "2") (pinfunction "2_2") (pintype "bidirectional"))
      (node (ref "UART5") (pin "2") (pinfunction "2_2") (pintype "bidirectional"))
    )
    (net (code "70") (name "5.0V") (class "Default")
      (node (ref "5VREG") (pin "3") (pinfunction "FB_3") (pintype "output"))
      (node (ref "C5") (pin "1") (pinfunction "1_1") (pintype "passive"))
      (node (ref "GPS") (pin "5") (pinfunction "5_5") (pintype "bidirectional"))
      (node (ref "L1") (pin "2") (pinfunction "2_2") (pintype "passive"))
      (node (ref "PWR") (pin "4") (pinfunction "4_4") (pintype "bidirectional"))
    )
    (net (code "71") (name "GND") (class "Default")
      (node (ref "5VREG") (pin "4") (pinfunction "SD_4") (pintype "input"))
      (node (ref "5VREG") (pin "5") (pinfunction "GND_5") (pintype "power_in"))
      (node (ref "5VREG") (pin "6") (pinfunction "GND1_6") (pintype "input"))
      (node (ref "5VREG") (pin "7") (pinfunction "GND2_7") (pintype "passive"))
      (node (ref "5VREG") (pin "8") (pinfunction "GND3_8") (pintype "power_in"))
      (node (ref "6V_REG") (pin "3") (pinfunction "GND_3") (pintype "bidirectional"))
      (node (ref "ADC") (pin "1") (pinfunction "1_1") (pintype "bidirectional"))
      (node (ref "BMP") (pin "7") (pinfunction "GND_7") (pintype "power_in"))
      (node (ref "C10") (pin "1") (pinfunction "1_1") (pintype "passive"))
      (node (ref "C11") (pin "-") (pinfunction "-_-") (pintype "passive"))
      (node (ref "C12") (pin "2") (pinfunction "2_2") (pintype "passive"))
      (node (ref "C13") (pin "2") (pinfunction "2_2") (pintype "passive"))
      (node (ref "C14") (pin "1") (pinfunction "1_1") (pintype "passive"))
      (node (ref "C16") (pin "2") (pinfunction "2_2") (pintype "passive"))
      (node (ref "C2") (pin "1") (pinfunction "1_1") (pintype "passive"))
      (node (ref "C20") (pin "1") (pinfunction "1_1") (pintype "passive"))
      (node (ref "C21") (pin "1") (pinfunction "1_1") (pintype "passive"))
      (node (ref "C23") (pin "1") (pinfunction "1_1") (pintype "passive"))
      (node (ref "C24") (pin "1") (pinfunction "1_1") (pintype "passive"))
      (node (ref "C25") (pin "2") (pinfunction "2_2") (pintype "passive"))
      (node (ref "C26") (pin "1") (pinfunction "1_1") (pintype "passive"))
      (node (ref "C3") (pin "2") (pinfunction "2_2") (pintype "passive"))
      (node (ref "C4") (pin "1") (pinfunction "1_1") (pintype "passive"))
      (node (ref "C5") (pin "2") (pinfunction "2_2") (pintype "passive"))
      (node (ref "C6") (pin "2") (pinfunction "2_2") (pintype "passive"))
      (node (ref "C7") (pin "2") (pinfunction "2_2") (pintype "passive"))
      (node (ref "C8") (pin "2") (pinfunction "2_2") (pintype "passive"))
      (node (ref "C9") (pin "2") (pinfunction "2_2") (pintype "passive"))
      (node (ref "CHG_IC") (pin "10") (pinfunction "VSS_10") (pintype "power_in"))
      (node (ref "CHG_IC") (pin "16") (pinfunction "~{CE}_16") (pintype "input"))
      (node (ref "CHG_IC") (pin "17") (pinfunction "PGND_17") (pintype "input"))
      (node (ref "CHG_IC") (pin "18") (pinfunction "PGND_18") (pintype "input"))
      (node (ref "CHG_IC") (pin "EXP") (pinfunction "PGND_EXP") (pintype "input"))
      (node (ref "CHG_IC") (pin "EXP@10") (pinfunction "PGND_EXP@10") (pintype "input"))
      (node (ref "CHG_IC") (pin "EXP@11") (pinfunction "PGND_EXP@11") (pintype "input"))
      (node (ref "CHG_IC") (pin "EXP@12") (pinfunction "PGND_EXP@12") (pintype "input"))
      (node (ref "CHG_IC") (pin "EXP@7") (pinfunction "PGND_EXP@7") (pintype "input"))
      (node (ref "CHG_IC") (pin "EXP@8") (pinfunction "PGND_EXP@8") (pintype "input"))
      (node (ref "CHG_IC") (pin "EXP@9") (pinfunction "PGND_EXP@9") (pintype "input"))
      (node (ref "CHG_IC") (pin "GND@1") (pinfunction "PGND_GND@1") (pintype "input"))
      (node (ref "CHG_IC") (pin "GND@2") (pinfunction "PGND_GND@2") (pintype "input"))
      (node (ref "CHG_IC") (pin "GND@3") (pinfunction "PGND_GND@3") (pintype "input"))
      (node (ref "CHG_IC") (pin "GND@4") (pinfunction "PGND_GND@4") (pintype "input"))
      (node (ref "CHG_IC") (pin "GND@6") (pinfunction "PGND_GND@6") (pintype "input"))
      (node (ref "D1") (pin "A") (pinfunction "A_A") (pintype "passive"))
      (node (ref "D9") (pin "A") (pinfunction "A_A") (pintype "passive"))
      (node (ref "DSM2") (pin "P$2") (pinfunction "2_P$2") (pintype "bidirectional"))
      (node (ref "E1") (pin "1") (pinfunction "1_1") (pintype "bidirectional"))
      (node (ref "E2") (pin "1") (pinfunction "1_1") (pintype "bidirectional"))
      (node (ref "E3") (pin "1") (pinfunction "1_1") (pintype "bidirectional"))
      (node (ref "E4") (pin "1") (pinfunction "1_1") (pintype "bidirectional"))
      (node (ref "GPS") (pin "2") (pinfunction "2_2") (pintype "bidirectional"))
      (node (ref "GPS") (pin "6") (pinfunction "6_6") (pintype "bidirectional"))
      (node (ref "H1") (pin "10") (pinfunction "PGND2_10") (pintype "bidirectional"))
      (node (ref "H1") (pin "18") (pinfunction "GND_18") (pintype "bidirectional"))
      (node (ref "H1") (pin "3") (pinfunction "PGND1_3") (pintype "bidirectional"))
      (node (ref "H1") (pin "4") (pinfunction "PGND1_4") (pintype "bidirectional"))
      (node (ref "H1") (pin "9") (pinfunction "PGND2_9") (pintype "bidirectional"))
      (node (ref "H2") (pin "10") (pinfunction "PGND2_10") (pintype "bidirectional"))
      (node (ref "H2") (pin "18") (pinfunction "GND_18") (pintype "bidirectional"))
      (node (ref "H2") (pin "3") (pinfunction "PGND1_3") (pintype "bidirectional"))
      (node (ref "H2") (pin "4") (pinfunction "PGND1_4") (pintype "bidirectional"))
      (node (ref "H2") (pin "9") (pinfunction "PGND2_9") (pintype "bidirectional"))
      (node (ref "I2C1") (pin "1") (pinfunction "1_1") (pintype "bidirectional"))
      (node (ref "IMU") (pin "1") (pinfunction "CLKIN_1") (pintype "bidirectional"))
      (node (ref "IMU") (pin "11") (pinfunction "FSYNC_11") (pintype "bidirectional"))
      (node (ref "IMU") (pin "15") (pinfunction "GND_15") (pintype "bidirectional"))
      (node (ref "IMU") (pin "17") (pinfunction "GND_17") (pintype "bidirectional"))
      (node (ref "IMU") (pin "18") (pinfunction "GND_18") (pintype "bidirectional"))
      (node (ref "IMU") (pin "9") (pinfunction "AD0_9") (pintype "bidirectional"))
      (node (ref "JACK") (pin "2") (pinfunction "2_2") (pintype "passive"))
      (node (ref "JACK") (pin "3") (pinfunction "3_3") (pintype "passive"))
      (node (ref "MODE") (pin "P$1") (pinfunction "1_P$1") (pintype "passive"))
      (node (ref "PAUSE") (pin "P$1") (pinfunction "1_P$1") (pintype "passive"))
      (node (ref "POWER") (pin "P$1") (pinfunction "1_P$1") (pintype "passive"))
      (node (ref "PWR") (pin "1") (pinfunction "1_1") (pintype "bidirectional"))
      (node (ref "PWR") (pin "2") (pinfunction "2_2") (pintype "bidirectional"))
      (node (ref "Q4") (pin "5") (pinfunction "D_5") (pintype "passive"))
      (node (ref "Q4") (pin "6") (pinfunction "D_6") (pintype "passive"))
      (node (ref "Q4") (pin "7") (pinfunction "D_7") (pintype "passive"))
      (node (ref "Q4") (pin "8") (pinfunction "D_8") (pintype "passive"))
      (node (ref "R14") (pin "2") (pinfunction "2_2") (pintype "passive"))
      (node (ref "R21") (pin "2") (pinfunction "2_2") (pintype "passive"))
      (node (ref "R22") (pin "2") (pinfunction "2_2") (pintype "passive"))
      (node (ref "R24") (pin "2") (pinfunction "2_2") (pintype "passive"))
      (node (ref "R25") (pin "2") (pinfunction "2_2") (pintype "passive"))
      (node (ref "R29") (pin "2") (pinfunction "2_2") (pintype "passive"))
      (node (ref "R31") (pin "2") (pinfunction "2_2") (pintype "passive"))
      (node (ref "R32") (pin "2") (pinfunction "2_2") (pintype "passive"))
      (node (ref "R33") (pin "2") (pinfunction "2_2") (pintype "passive"))
      (node (ref "R47") (pin "1") (pinfunction "1_1") (pintype "passive"))
      (node (ref "R48") (pin "1") (pinfunction "1_1") (pintype "passive"))
      (node (ref "R5") (pin "1") (pinfunction "1_1") (pintype "passive"))
      (node (ref "R6") (pin "1") (pinfunction "1_1") (pintype "passive"))
      (node (ref "R8") (pin "2") (pinfunction "2_2") (pintype "passive"))
      (node (ref "RESET") (pin "P$1") (pinfunction "1_P$1") (pintype "passive"))
      (node (ref "SPI1.1") (pin "1") (pinfunction "1_1") (pintype "bidirectional"))
      (node (ref "SPI1.2") (pin "1") (pinfunction "1_1") (pintype "bidirectional"))
      (node (ref "U$1") (pin "P$13") (pinfunction "GND_P$13") (pintype "bidirectional"))
      (node (ref "U$1") (pin "P$14") (pinfunction "GND_P$14") (pintype "bidirectional"))
      (node (ref "U$1") (pin "P$15") (pinfunction "GND_P$15") (pintype "bidirectional"))
      (node (ref "U$1") (pin "P$16") (pinfunction "GND_P$16") (pintype "bidirectional"))
      (node (ref "U$1") (pin "P$17") (pinfunction "GND_P$17") (pintype "bidirectional"))
      (node (ref "U$1") (pin "P$18") (pinfunction "GND_P$18") (pintype "bidirectional"))
      (node (ref "U$1") (pin "P$23") (pinfunction "GND_P$23") (pintype "bidirectional"))
      (node (ref "U$1") (pin "P$24") (pinfunction "GND_P$24") (pintype "bidirectional"))
      (node (ref "U1") (pin "18") (pinfunction "GND_18") (pintype "bidirectional"))
      (node (ref "U1") (pin "20") (pinfunction "RESV_20") (pintype "bidirectional"))
      (node (ref "U1") (pin "25") (pinfunction "PAD_25") (pintype "bidirectional"))
      (node (ref "U1") (pin "9") (pinfunction "AD0/SDO_9") (pintype "bidirectional"))
      (node (ref "UART1") (pin "1") (pinfunction "1_1") (pintype "bidirectional"))
      (node (ref "UART5") (pin "1") (pinfunction "1_1") (pintype "bidirectional"))
    )
    (net (code "72") (name "Net-(5VREG-OUT)") (class "Default")
      (node (ref "5VREG") (pin "2") (pinfunction "OUT_2") (pintype "output"))
      (node (ref "D1") (pin "C") (pinfunction "C_C") (pintype "passive"))
      (node (ref "L1") (pin "1") (pinfunction "1_1") (pintype "passive"))
    )
    (net (code "73") (name "Net-(5VREG-VIN)") (class "Default")
      (node (ref "5VREG") (pin "1") (pinfunction "VIN_1") (pintype "input"))
      (node (ref "C3") (pin "1") (pinfunction "1_1") (pintype "passive"))
      (node (ref "D2") (pin "C") (pinfunction "C_C") (pintype "passive"))
      (node (ref "D3") (pin "C") (pinfunction "C_C") (pintype "passive"))
    )
    (net (code "74") (name "Net-(6V_REG-BS)") (class "Default")
      (node (ref "6V_REG") (pin "2") (pinfunction "BS_2") (pintype "bidirectional"))
      (node (ref "C22") (pin "1") (pinfunction "1_1") (pintype "passive"))
    )
    (net (code "75") (name "Net-(6V_REG-COMP)") (class "Default")
      (node (ref "6V_REG") (pin "5") (pinfunction "COMP_5") (pintype "bidirectional"))
      (node (ref "R45") (pin "2") (pinfunction "2_2") (pintype "passive"))
    )
    (net (code "76") (name "Net-(6V_REG-FB)") (class "Default")
      (node (ref "6V_REG") (pin "6") (pinfunction "FB_6") (pintype "bidirectional"))
      (node (ref "R48") (pin "2") (pinfunction "2_2") (pintype "passive"))
      (node (ref "R49") (pin "1") (pinfunction "1_1") (pintype "passive"))
    )
    (net (code "77") (name "Net-(6V_REG-FSW)") (class "Default")
      (node (ref "6V_REG") (pin "4") (pinfunction "FSW_4") (pintype "bidirectional"))
      (node (ref "R47") (pin "2") (pinfunction "2_2") (pintype "passive"))
    )
    (net (code "78") (name "Net-(6V_REG-LX)") (class "Default")
      (node (ref "6V_REG") (pin "1") (pinfunction "LX_1") (pintype "bidirectional"))
      (node (ref "C22") (pin "2") (pinfunction "2_2") (pintype "passive"))
      (node (ref "D9") (pin "C") (pinfunction "C_C") (pintype "passive"))
      (node (ref "L3") (pin "1") (pinfunction "1_1") (pintype "passive"))
    )
    (net (code "79") (name "Net-(6V_REG-SS)") (class "Default")
      (node (ref "6V_REG") (pin "7") (pinfunction "SS_7") (pintype "bidirectional"))
      (node (ref "C21") (pin "2") (pinfunction "2_2") (pintype "passive"))
    )
    (net (code "80") (name "Net-(BAL-CD)") (class "Default")
      (node (ref "BAL") (pin "4") (pinfunction "CD_4") (pintype "bidirectional"))
      (node (ref "C19") (pin "1") (pinfunction "1_1") (pintype "passive"))
    )
    (net (code "81") (name "Net-(BAL-VC1)") (class "Default")
      (node (ref "BAL") (pin "2") (pinfunction "VC1_2") (pintype "bidirectional"))
      (node (ref "C17") (pin "1") (pinfunction "1_1") (pintype "passive"))
      (node (ref "C18") (pin "2") (pinfunction "2_2") (pintype "passive"))
      (node (ref "R30") (pin "2") (pinfunction "2_2") (pintype "passive"))
    )
    (net (code "82") (name "Net-(BAL-VC1_CB)") (class "Default")
      (node (ref "BAL") (pin "3") (pinfunction "VC1_CB_3") (pintype "bidirectional"))
      (node (ref "R27") (pin "2") (pinfunction "2_2") (pintype "passive"))
    )
    (net (code "83") (name "Net-(BAL-VC2)") (class "Default")
      (node (ref "BAL") (pin "1") (pinfunction "VC2_1") (pintype "bidirectional"))
      (node (ref "C17") (pin "2") (pinfunction "2_2") (pintype "passive"))
      (node (ref "R28") (pin "2") (pinfunction "2_2") (pintype "passive"))
    )
    (net (code "84") (name "Net-(BAL-VDD)") (class "Default")
      (node (ref "BAL") (pin "7") (pinfunction "VDD_7") (pintype "bidirectional"))
      (node (ref "C1") (pin "1") (pinfunction "1_1") (pintype "passive"))
      (node (ref "R34") (pin "2") (pinfunction "2_2") (pintype "passive"))
    )
    (net (code "85") (name "Net-(C23-Pad2)") (class "Default")
      (node (ref "C23") (pin "2") (pinfunction "2_2") (pintype "passive"))
      (node (ref "L3") (pin "2") (pinfunction "2_2") (pintype "passive"))
      (node (ref "R49") (pin "2") (pinfunction "2_2") (pintype "passive"))
      (node (ref "U$1") (pin "P$10") (pinfunction "PWR_P$10") (pintype "bidirectional"))
      (node (ref "U$1") (pin "P$11") (pinfunction "PWR_P$11") (pintype "bidirectional"))
      (node (ref "U$1") (pin "P$12") (pinfunction "PWR_P$12") (pintype "bidirectional"))
      (node (ref "U$1") (pin "P$21") (pinfunction "PWR_P$21") (pintype "bidirectional"))
      (node (ref "U$1") (pin "P$22") (pinfunction "PWR_P$22") (pintype "bidirectional"))
      (node (ref "U$1") (pin "P$7") (pinfunction "PWR_P$7") (pintype "bidirectional"))
      (node (ref "U$1") (pin "P$8") (pinfunction "PWR_P$8") (pintype "bidirectional"))
      (node (ref "U$1") (pin "P$9") (pinfunction "PWR_P$9") (pintype "bidirectional"))
    )
    (net (code "86") (name "Net-(C24-Pad2)") (class "Default")
      (node (ref "C24") (pin "2") (pinfunction "2_2") (pintype "passive"))
      (node (ref "R45") (pin "1") (pinfunction "1_1") (pintype "passive"))
    )
    (net (code "87") (name "Net-(CHG-PadC)") (class "Default")
      (node (ref "CHG") (pin "C") (pinfunction "C_C") (pintype "passive"))
      (node (ref "R3") (pin "2") (pinfunction "2_2") (pintype "passive"))
    )
    (net (code "88") (name "Net-(CHG_IC-FB)") (class "Default")
      (node (ref "CHG_IC") (pin "13") (pinfunction "FB_13") (pintype "input"))
      (node (ref "R7") (pin "2") (pinfunction "2_2") (pintype "passive"))
      (node (ref "R8") (pin "1") (pinfunction "1_1") (pintype "passive"))
    )
    (net (code "89") (name "Net-(CHG_IC-ISET1)") (class "Default")
      (node (ref "CHG_IC") (pin "8") (pinfunction "ISET1_8") (pintype "bidirectional"))
      (node (ref "R6") (pin "2") (pinfunction "2_2") (pintype "passive"))
    )
    (net (code "90") (name "Net-(CHG_IC-ISET2)") (class "Default")
      (node (ref "CHG_IC") (pin "9") (pinfunction "ISET2_9") (pintype "bidirectional"))
      (node (ref "R5") (pin "2") (pinfunction "2_2") (pintype "passive"))
    )
    (net (code "91") (name "Net-(CHG_IC-OUT-Pad1)") (class "Default")
      (node (ref "CHG_IC") (pin "1") (pinfunction "OUT_1") (pintype "output"))
      (node (ref "CHG_IC") (pin "20") (pinfunction "OUT_20") (pintype "input"))
      (node (ref "L2") (pin "1") (pinfunction "1_1") (pintype "passive"))
    )
    (net (code "92") (name "Net-(CHG_IC-SNS)") (class "Default")
      (node (ref "C7") (pin "1") (pinfunction "1_1") (pintype "passive"))
      (node (ref "CHG_IC") (pin "15") (pinfunction "SNS_15") (pintype "input"))
      (node (ref "L2") (pin "2") (pinfunction "2_2") (pintype "passive"))
      (node (ref "R4") (pin "2") (pinfunction "2_2") (pintype "passive"))
    )
    (net (code "93") (name "Net-(CHG_IC-STAT1)") (class "Default")
      (node (ref "CHG_IC") (pin "2") (pinfunction "STAT1_2") (pintype "output"))
      (node (ref "R3") (pin "1") (pinfunction "1_1") (pintype "passive"))
    )
    (net (code "94") (name "Net-(CHG_IC-STAT2)") (class "Default")
      (node (ref "CHG_IC") (pin "19") (pinfunction "STAT2_19") (pintype "output"))
      (node (ref "R2") (pin "1") (pinfunction "1_1") (pintype "passive"))
    )
    (net (code "95") (name "Net-(CHG_IC-TS)") (class "Default")
      (node (ref "CHG_IC") (pin "12") (pinfunction "TS_12") (pintype "input"))
      (node (ref "R23") (pin "2") (pinfunction "2_2") (pintype "passive"))
      (node (ref "R24") (pin "1") (pinfunction "1_1") (pintype "passive"))
    )
    (net (code "96") (name "Net-(CHG_IC-TTC)") (class "Default")
      (node (ref "C4") (pin "2") (pinfunction "2_2") (pintype "passive"))
      (node (ref "CHG_IC") (pin "7") (pinfunction "TTC_7") (pintype "passive"))
    )
    (net (code "97") (name "Net-(CHG_IC-VTSB)") (class "Default")
      (node (ref "C10") (pin "2") (pinfunction "2_2") (pintype "passive"))
      (node (ref "CHG_IC") (pin "11") (pinfunction "VTSB_11") (pintype "output"))
      (node (ref "R23") (pin "1") (pinfunction "1_1") (pintype "passive"))
    )
    (net (code "98") (name "Net-(D4-PadC)") (class "Default")
      (node (ref "D4") (pin "C") (pinfunction "C_C") (pintype "passive"))
      (node (ref "R31") (pin "1") (pinfunction "1_1") (pintype "passive"))
    )
    (net (code "99") (name "Net-(D5-PadC)") (class "Default")
      (node (ref "D5") (pin "C") (pinfunction "C_C") (pintype "passive"))
      (node (ref "R29") (pin "1") (pinfunction "1_1") (pintype "passive"))
    )
    (net (code "100") (name "Net-(D6-PadC)") (class "Default")
      (node (ref "D6") (pin "C") (pinfunction "C_C") (pintype "passive"))
      (node (ref "R33") (pin "1") (pinfunction "1_1") (pintype "passive"))
    )
    (net (code "101") (name "Net-(D7-PadC)") (class "Default")
      (node (ref "D7") (pin "C") (pinfunction "C_C") (pintype "passive"))
      (node (ref "R32") (pin "1") (pinfunction "1_1") (pintype "passive"))
    )
    (net (code "102") (name "Net-(FULL-PadC)") (class "Default")
      (node (ref "FULL") (pin "C") (pinfunction "C_C") (pintype "passive"))
      (node (ref "R2") (pin "2") (pinfunction "2_2") (pintype "passive"))
    )
    (net (code "103") (name "Net-(GRN-PadC)") (class "Default")
      (node (ref "GRN") (pin "C") (pinfunction "C_C") (pintype "passive"))
      (node (ref "R22") (pin "1") (pinfunction "1_1") (pintype "passive"))
    )
    (net (code "104") (name "Net-(IMU-CPOUT)") (class "Default")
      (node (ref "C9") (pin "1") (pinfunction "1_1") (pintype "passive"))
      (node (ref "IMU") (pin "20") (pinfunction "CPOUT_20") (pintype "bidirectional"))
    )
    (net (code "105") (name "Net-(IMU-REGOUT)") (class "Default")
      (node (ref "C8") (pin "1") (pinfunction "1_1") (pintype "passive"))
      (node (ref "IMU") (pin "10") (pinfunction "REGOUT_10") (pintype "bidirectional"))
    )
    (net (code "106") (name "Net-(M1-1)") (class "Default")
      (node (ref "H1") (pin "5") (pinfunction "A02_5") (pintype "bidirectional"))
      (node (ref "H1") (pin "6") (pinfunction "A02_6") (pintype "bidirectional"))
      (node (ref "M1") (pin "P$1") (pinfunction "1_P$1") (pintype "bidirectional"))
    )
    (net (code "107") (name "Net-(M1-2)") (class "Default")
      (node (ref "H1") (pin "1") (pinfunction "A01_1") (pintype "bidirectional"))
      (node (ref "H1") (pin "2") (pinfunction "A01_2") (pintype "bidirectional"))
      (node (ref "M1") (pin "P$2") (pinfunction "2_P$2") (pintype "bidirectional"))
    )
    (net (code "108") (name "Net-(M2-1)") (class "Default")
      (node (ref "H1") (pin "11") (pinfunction "B01_11") (pintype "bidirectional"))
      (node (ref "H1") (pin "12") (pinfunction "B01_12") (pintype "bidirectional"))
      (node (ref "M2") (pin "P$1") (pinfunction "1_P$1") (pintype "bidirectional"))
    )
    (net (code "109") (name "Net-(M2-2)") (class "Default")
      (node (ref "H1") (pin "7") (pinfunction "B02_7") (pintype "bidirectional"))
      (node (ref "H1") (pin "8") (pinfunction "B02_8") (pintype "bidirectional"))
      (node (ref "M2") (pin "P$2") (pinfunction "2_P$2") (pintype "bidirectional"))
    )
    (net (code "110") (name "Net-(M3-1)") (class "Default")
      (node (ref "H2") (pin "1") (pinfunction "A01_1") (pintype "bidirectional"))
      (node (ref "H2") (pin "2") (pinfunction "A01_2") (pintype "bidirectional"))
      (node (ref "M3") (pin "P$1") (pinfunction "1_P$1") (pintype "bidirectional"))
    )
    (net (code "111") (name "Net-(M3-2)") (class "Default")
      (node (ref "H2") (pin "5") (pinfunction "A02_5") (pintype "bidirectional"))
      (node (ref "H2") (pin "6") (pinfunction "A02_6") (pintype "bidirectional"))
      (node (ref "M3") (pin "P$2") (pinfunction "2_P$2") (pintype "bidirectional"))
    )
    (net (code "112") (name "Net-(M4-1)") (class "Default")
      (node (ref "H2") (pin "7") (pinfunction "B02_7") (pintype "bidirectional"))
      (node (ref "H2") (pin "8") (pinfunction "B02_8") (pintype "bidirectional"))
      (node (ref "M4") (pin "P$1") (pinfunction "1_P$1") (pintype "bidirectional"))
    )
    (net (code "113") (name "Net-(M4-2)") (class "Default")
      (node (ref "H2") (pin "11") (pinfunction "B01_11") (pintype "bidirectional"))
      (node (ref "H2") (pin "12") (pinfunction "B01_12") (pintype "bidirectional"))
      (node (ref "M4") (pin "P$2") (pinfunction "2_P$2") (pintype "bidirectional"))
    )
    (net (code "114") (name "Net-(PROT-VDD)") (class "Default")
      (node (ref "C15") (pin "2") (pinfunction "2_2") (pintype "passive"))
      (node (ref "PROT") (pin "5") (pinfunction "VDD_5") (pintype "bidirectional"))
      (node (ref "R44") (pin "2") (pinfunction "2_2") (pintype "passive"))
    )
    (net (code "115") (name "Net-(Q3-D-Pad5)") (class "Default")
      (node (ref "Q3") (pin "5") (pinfunction "D_5") (pintype "passive"))
      (node (ref "Q3") (pin "6") (pinfunction "D_6") (pintype "passive"))
      (node (ref "Q3") (pin "7") (pinfunction "D_7") (pintype "passive"))
      (node (ref "Q3") (pin "8") (pinfunction "D_8") (pintype "passive"))
      (node (ref "Q4") (pin "1") (pinfunction "S_1") (pintype "passive"))
      (node (ref "Q4") (pin "2") (pinfunction "S_2") (pintype "passive"))
      (node (ref "Q4") (pin "3") (pinfunction "S_3") (pintype "passive"))
    )
    (net (code "116") (name "Net-(R21-Pad1)") (class "Default")
      (node (ref "R21") (pin "1") (pinfunction "1_1") (pintype "passive"))
      (node (ref "RED") (pin "C") (pinfunction "C_C") (pintype "passive"))
    )
    (net (code "117") (name "Net-(U$1-1)") (class "Default")
      (node (ref "R36") (pin "2") (pinfunction "2_2") (pintype "passive"))
      (node (ref "U$1") (pin "P$1") (pinfunction "1_P$1") (pintype "bidirectional"))
    )
    (net (code "118") (name "Net-(U$1-2)") (class "Default")
      (node (ref "R37") (pin "2") (pinfunction "2_2") (pintype "passive"))
      (node (ref "U$1") (pin "P$2") (pinfunction "2_P$2") (pintype "bidirectional"))
    )
    (net (code "119") (name "Net-(U$1-3)") (class "Default")
      (node (ref "R38") (pin "2") (pinfunction "2_2") (pintype "passive"))
      (node (ref "U$1") (pin "P$3") (pinfunction "3_P$3") (pintype "bidirectional"))
    )
    (net (code "120") (name "Net-(U$1-4)") (class "Default")
      (node (ref "R39") (pin "2") (pinfunction "2_2") (pintype "passive"))
      (node (ref "U$1") (pin "P$4") (pinfunction "4_P$4") (pintype "bidirectional"))
    )
    (net (code "121") (name "Net-(U$1-5)") (class "Default")
      (node (ref "R40") (pin "2") (pinfunction "2_2") (pintype "passive"))
      (node (ref "U$1") (pin "P$5") (pinfunction "5_P$5") (pintype "bidirectional"))
    )
    (net (code "122") (name "Net-(U$1-6)") (class "Default")
      (node (ref "R41") (pin "2") (pinfunction "2_2") (pintype "passive"))
      (node (ref "U$1") (pin "P$6") (pinfunction "6_P$6") (pintype "bidirectional"))
    )
    (net (code "123") (name "Net-(U$1-7)") (class "Default")
      (node (ref "R42") (pin "2") (pinfunction "2_2") (pintype "passive"))
      (node (ref "U$1") (pin "P$19") (pinfunction "7_P$19") (pintype "bidirectional"))
    )
    (net (code "124") (name "Net-(U$1-8)") (class "Default")
      (node (ref "R43") (pin "2") (pinfunction "2_2") (pintype "passive"))
      (node (ref "U$1") (pin "P$20") (pinfunction "8_P$20") (pintype "bidirectional"))
    )
    (net (code "125") (name "Net-(U1-REGOUT)") (class "Default")
      (node (ref "C26") (pin "2") (pinfunction "2_2") (pintype "passive"))
      (node (ref "U1") (pin "10") (pinfunction "REGOUT_10") (pintype "bidirectional"))
    )
    (net (code "126") (name "VDC") (class "Default")
      (node (ref "C12") (pin "1") (pinfunction "1_1") (pintype "passive"))
      (node (ref "C14") (pin "2") (pinfunction "2_2") (pintype "passive"))
      (node (ref "CHG") (pin "A") (pinfunction "A_A") (pintype "passive"))
      (node (ref "CHG_IC") (pin "3") (pinfunction "IN1_3") (pintype "input"))
      (node (ref "CHG_IC") (pin "4") (pinfunction "IN2_4") (pintype "input"))
      (node (ref "CHG_IC") (pin "6") (pinfunction "VCC_6") (pintype "input"))
      (node (ref "D3") (pin "A") (pinfunction "A_A") (pintype "passive"))
      (node (ref "FULL") (pin "A") (pinfunction "A_A") (pintype "passive"))
      (node (ref "JACK") (pin "1") (pinfunction "1_1") (pintype "passive"))
      (node (ref "R1") (pin "1") (pinfunction "1_1") (pintype "passive"))
    )
    (net (code "127") (name "V_BATT") (class "Default")
      (node (ref "6V_REG") (pin "9") (pinfunction "VIN_9") (pintype "bidirectional"))
      (node (ref "C11") (pin "+") (pinfunction "+_+") (pintype "passive"))
      (node (ref "C20") (pin "2") (pinfunction "2_2") (pintype "passive"))
      (node (ref "CHG_IC") (pin "14") (pinfunction "BAT_14") (pintype "input"))
      (node (ref "D2") (pin "A") (pinfunction "A_A") (pintype "passive"))
      (node (ref "H1") (pin "13") (pinfunction "VM2_13") (pintype "bidirectional"))
      (node (ref "H1") (pin "14") (pinfunction "VM3_14") (pintype "bidirectional"))
      (node (ref "H1") (pin "24") (pinfunction "VM1_24") (pintype "bidirectional"))
      (node (ref "H2") (pin "13") (pinfunction "VM2_13") (pintype "bidirectional"))
      (node (ref "H2") (pin "14") (pinfunction "VM3_14") (pintype "bidirectional"))
      (node (ref "H2") (pin "24") (pinfunction "VM1_24") (pintype "bidirectional"))
      (node (ref "LIPO") (pin "P$1") (pinfunction "1_P$1") (pintype "passive"))
      (node (ref "R19") (pin "1") (pinfunction "1_1") (pintype "passive"))
      (node (ref "R28") (pin "1") (pinfunction "1_1") (pintype "passive"))
      (node (ref "R34") (pin "1") (pinfunction "1_1") (pintype "passive"))
      (node (ref "R4") (pin "1") (pinfunction "1_1") (pintype "passive"))
      (node (ref "R7") (pin "1") (pinfunction "1_1") (pintype "passive"))
    )
    (net (code "128") (name "unconnected-(CHG_IC-~{PG}-Pad5)") (class "Default")
      (node (ref "CHG_IC") (pin "5") (pinfunction "~{PG}_5") (pintype "output"))
    )
    (net (code "129") (name "unconnected-(GPS-Pad1)") (class "Default")
      (node (ref "GPS") (pin "1") (pinfunction "1_1") (pintype "bidirectional"))
    )
    (net (code "130") (name "unconnected-(IMU-CLKOUT-Pad22)") (class "Default")
      (node (ref "IMU") (pin "22") (pinfunction "CLKOUT_22") (pintype "bidirectional"))
    )
    (net (code "131") (name "unconnected-(IMU-E_SCL-Pad7)") (class "Default")
      (node (ref "IMU") (pin "7") (pinfunction "E_SCL_7") (pintype "bidirectional"))
    )
    (net (code "132") (name "unconnected-(IMU-E_SDA-Pad6)") (class "Default")
      (node (ref "IMU") (pin "6") (pinfunction "E_SDA_6") (pintype "bidirectional"))
    )
    (net (code "133") (name "unconnected-(PROT-CO-Pad3)") (class "Default")
      (node (ref "PROT") (pin "3") (pinfunction "CO_3") (pintype "bidirectional"))
    )
    (net (code "134") (name "unconnected-(PROT-DP-Pad4)") (class "Default")
      (node (ref "PROT") (pin "4") (pinfunction "DP_4") (pintype "bidirectional"))
    )
    (net (code "135") (name "unconnected-(U1-AUX_CL-Pad7)") (class "Default")
      (node (ref "U1") (pin "7") (pinfunction "AUX_CL_7") (pintype "bidirectional"))
    )
    (net (code "136") (name "unconnected-(U1-AUX_DA-Pad21)") (class "Default")
      (node (ref "U1") (pin "21") (pinfunction "AUX_DA_21") (pintype "bidirectional"))
    )
    (net (code "137") (name "unconnected-(U1-FSYNC-Pad11)") (class "Default")
      (node (ref "U1") (pin "11") (pinfunction "FSYNC_11") (pintype "bidirectional"))
    )
    (net (code "138") (name "unconnected-(U1-NC-Pad2)") (class "Default")
      (node (ref "U1") (pin "2") (pinfunction "NC_2") (pintype "bidirectional"))
    )
    (net (code "139") (name "unconnected-(U1-NC-Pad3)") (class "Default")
      (node (ref "U1") (pin "3") (pinfunction "NC_3") (pintype "bidirectional"))
    )
    (net (code "140") (name "unconnected-(U1-NC-Pad4)") (class "Default")
      (node (ref "U1") (pin "4") (pinfunction "NC_4") (pintype "bidirectional"))
    )
    (net (code "141") (name "unconnected-(U1-NC-Pad5)") (class "Default")
      (node (ref "U1") (pin "5") (pinfunction "NC_5") (pintype "bidirectional"))
    )
    (net (code "142") (name "unconnected-(U1-NC-Pad6)") (class "Default")
      (node (ref "U1") (pin "6") (pinfunction "NC_6") (pintype "bidirectional"))
    )
    (net (code "143") (name "unconnected-(U1-NC-Pad14)") (class "Default")
      (node (ref "U1") (pin "14") (pinfunction "NC_14") (pintype "bidirectional"))
    )
    (net (code "144") (name "unconnected-(U1-NC-Pad15)") (class "Default")
      (node (ref "U1") (pin "15") (pinfunction "NC_15") (pintype "bidirectional"))
    )
    (net (code "145") (name "unconnected-(U1-NC-Pad16)") (class "Default")
      (node (ref "U1") (pin "16") (pinfunction "NC_16") (pintype "bidirectional"))
    )
    (net (code "146") (name "unconnected-(U1-NC-Pad17)") (class "Default")
      (node (ref "U1") (pin "17") (pinfunction "NC_17") (pintype "bidirectional"))
    )
    (net (code "147") (name "unconnected-(U1-NCS-Pad22)") (class "Default")
      (node (ref "U1") (pin "22") (pinfunction "NCS_22") (pintype "bidirectional"))
    )
    (net (code "148") (name "unconnected-(U1-RESV-Pad19)") (class "Default")
      (node (ref "U1") (pin "19") (pinfunction "RESV_19") (pintype "bidirectional"))
    )
  )
)
